# ThreeDigitDisplay.net
KiCad netlist of a schematic drawn in EAGLE
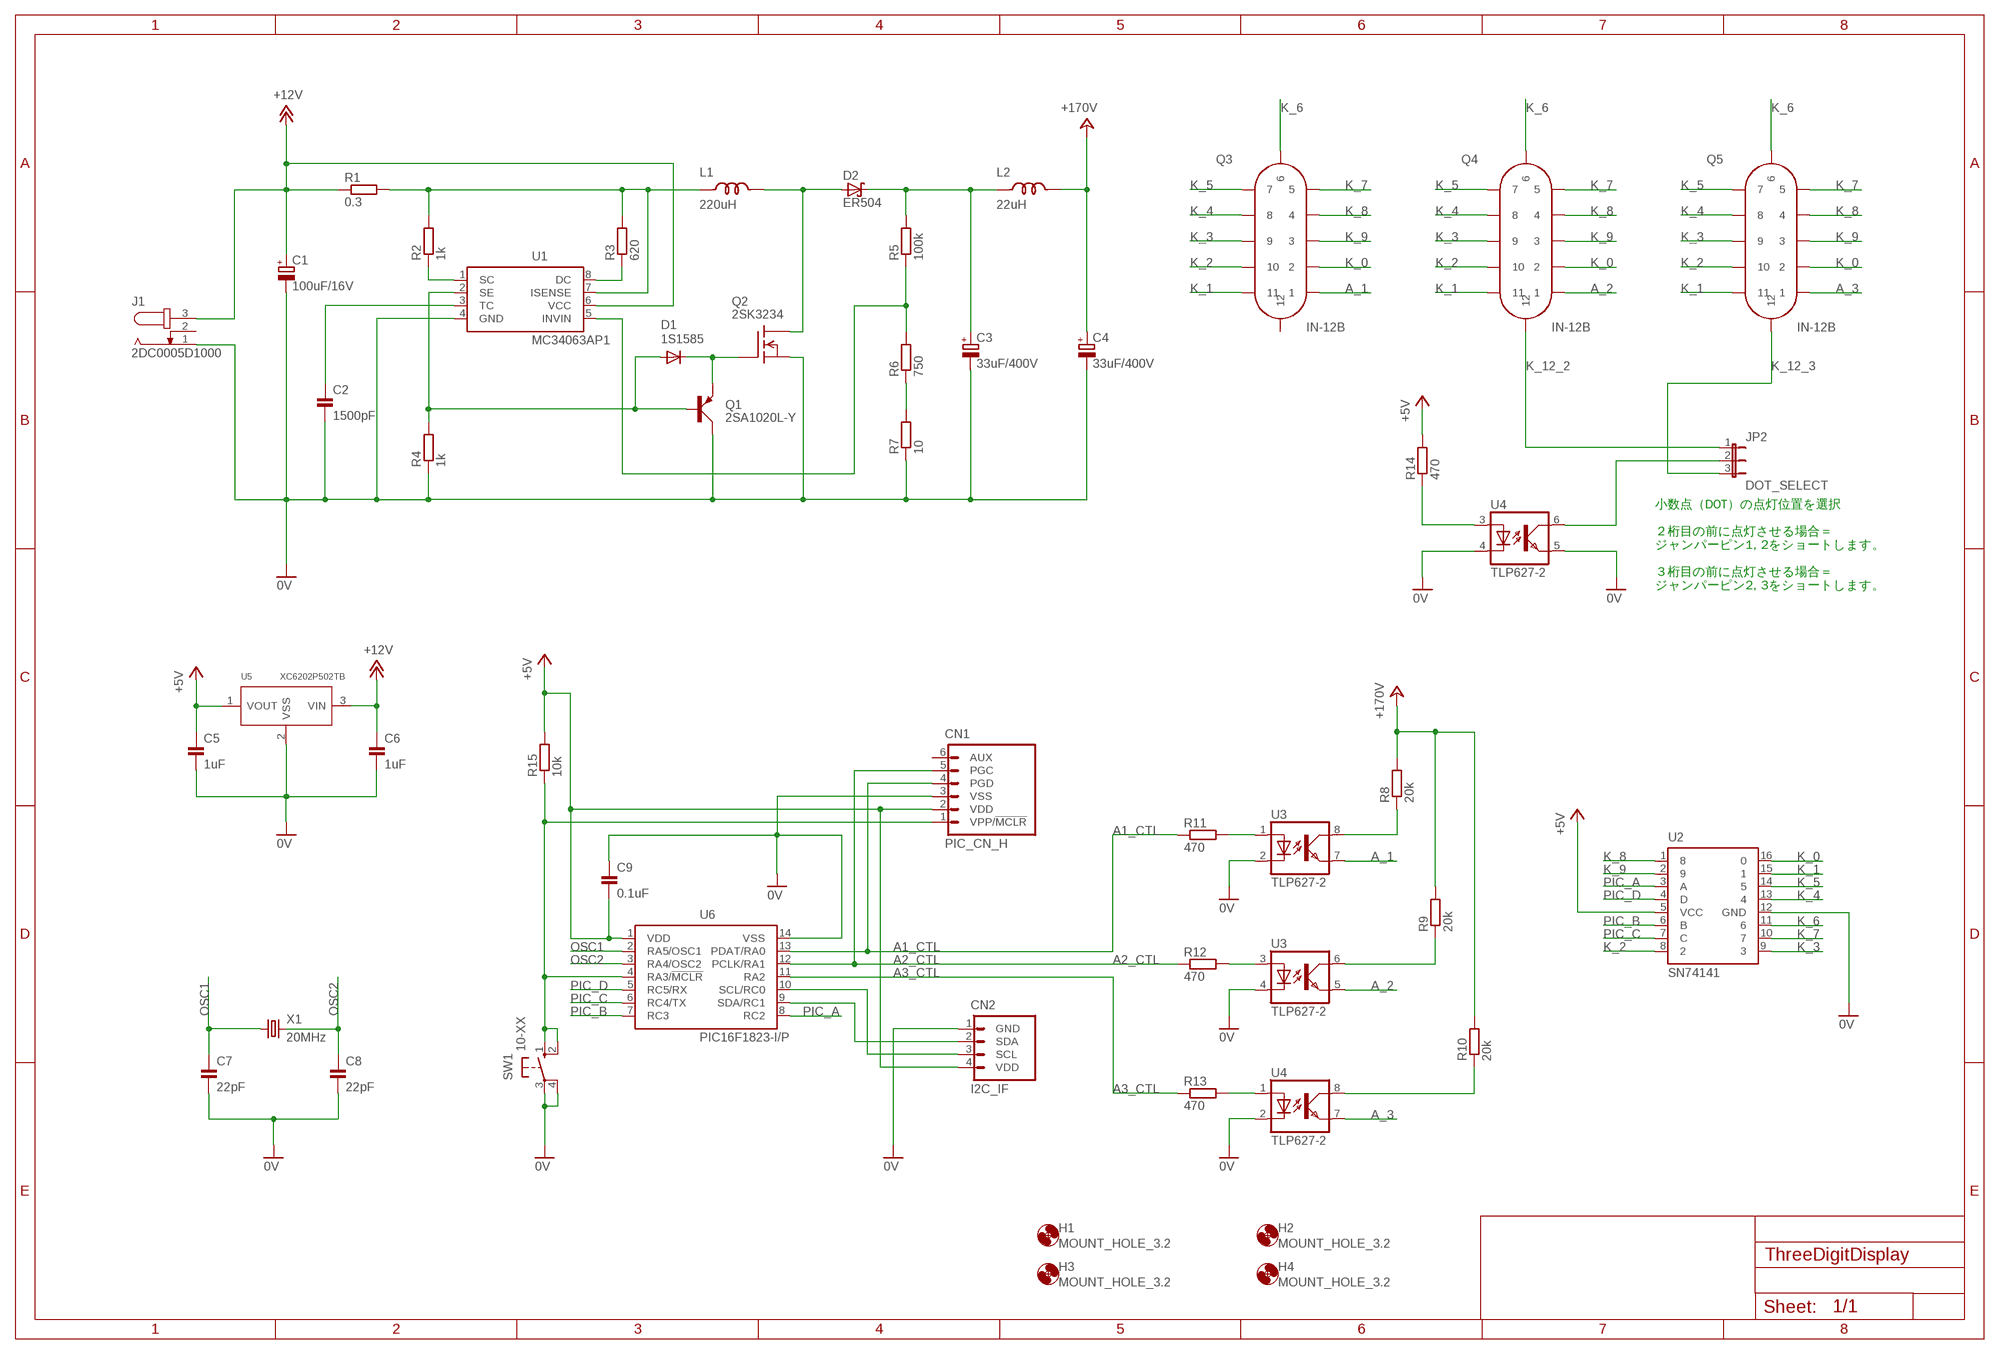
[diagram p0: schematic, sheet 1]

(export (version "E")
  (design (tool "Eeschema 10.0.6"))
  (components
    (comp (ref "C1")
      (value "100uF/16V")
      (footprint "eagle-import:ELECAP_200MIL")
      (libsource (lib "eagle-import") (part "ELECAP_200MIL"))
    )
    (comp (ref "C2")
      (value "1500pF")
      (footprint "eagle-import:CAP_200MIL")
      (libsource (lib "eagle-import") (part "CAP_200MIL"))
    )
    (comp (ref "C3")
      (value "33uF/400V")
      (footprint "eagle-import:ELECAP_300MIL")
      (libsource (lib "eagle-import") (part "ELECAP_300MIL"))
    )
    (comp (ref "C4")
      (value "33uF/400V")
      (footprint "eagle-import:ELECAP_300MIL")
      (libsource (lib "eagle-import") (part "ELECAP_300MIL"))
    )
    (comp (ref "C5")
      (value "1uF")
      (footprint "eagle-import:CAP_200MIL")
      (libsource (lib "eagle-import") (part "CAP_200MIL"))
    )
    (comp (ref "C6")
      (value "1uF")
      (footprint "eagle-import:CAP_200MIL")
      (libsource (lib "eagle-import") (part "CAP_200MIL"))
    )
    (comp (ref "C7")
      (value "22pF")
      (footprint "eagle-import:CAP_200MIL")
      (libsource (lib "eagle-import") (part "CAP_200MIL"))
    )
    (comp (ref "C8")
      (value "22pF")
      (footprint "eagle-import:CAP_200MIL")
      (libsource (lib "eagle-import") (part "CAP_200MIL"))
    )
    (comp (ref "C9")
      (value "0.1uF")
      (footprint "eagle-import:CAP_200MIL")
      (libsource (lib "eagle-import") (part "CAP_200MIL"))
    )
    (comp (ref "CN1")
      (value "PIC_CN_H")
      (footprint "eagle-import:HEADER_6PIN")
      (libsource (lib "eagle-import") (part "PIC_CN_H"))
    )
    (comp (ref "CN2")
      (value "I2C_IF")
      (footprint "eagle-import:I2C_IF")
      (libsource (lib "eagle-import") (part "I2C_IF"))
    )
    (comp (ref "D1")
      (value "1S1585")
      (footprint "eagle-import:DIODE-200MIL")
      (libsource (lib "eagle-import") (part "1S1585"))
    )
    (comp (ref "D2")
      (value "ER504")
      (footprint "eagle-import:DIODE-500MIL")
      (libsource (lib "eagle-import") (part "ER504"))
    )
    (comp (ref "H1")
      (value "MOUNT_HOLE_3.2")
      (footprint "eagle-import:3,2")
      (libsource (lib "eagle-import") (part "MOUNT_HOLE_3.2"))
    )
    (comp (ref "H2")
      (value "MOUNT_HOLE_3.2")
      (footprint "eagle-import:3,2")
      (libsource (lib "eagle-import") (part "MOUNT_HOLE_3.2"))
    )
    (comp (ref "H3")
      (value "MOUNT_HOLE_3.2")
      (footprint "eagle-import:3,2")
      (libsource (lib "eagle-import") (part "MOUNT_HOLE_3.2"))
    )
    (comp (ref "H4")
      (value "MOUNT_HOLE_3.2")
      (footprint "eagle-import:3,2")
      (libsource (lib "eagle-import") (part "MOUNT_HOLE_3.2"))
    )
    (comp (ref "J1")
      (value "2DC0005D1000")
      (footprint "eagle-import:DCJACK_2.1_5.5")
      (libsource (lib "eagle-import") (part "2DC0005D1000"))
    )
    (comp (ref "JP2")
      (value "DOT_SELECT")
      (footprint "eagle-import:JP2")
      (libsource (lib "eagle-import") (part "JP2E"))
    )
    (comp (ref "L1")
      (value "220uH")
      (footprint "eagle-import:TOROID_COIL-300MIL")
      (libsource (lib "eagle-import") (part "TC5026-220UH-050"))
    )
    (comp (ref "L2")
      (value "22uH")
      (footprint "eagle-import:TOROID_COIL-300MIL")
      (libsource (lib "eagle-import") (part "TC5026-22UH-060"))
    )
    (comp (ref "Q1")
      (value "2SA1020L-Y")
      (footprint "eagle-import:TO-92NL")
      (libsource (lib "eagle-import") (part "2SA1020L-Y"))
    )
    (comp (ref "Q2")
      (value "2SK3234")
      (footprint "eagle-import:TO-220")
      (libsource (lib "eagle-import") (part "2SK3234"))
    )
    (comp (ref "Q3")
      (value "IN-12B")
      (footprint "eagle-import:IN-12")
      (libsource (lib "eagle-import") (part "IN-12B"))
    )
    (comp (ref "Q4")
      (value "IN-12B")
      (footprint "eagle-import:IN-12")
      (libsource (lib "eagle-import") (part "IN-12B"))
    )
    (comp (ref "Q5")
      (value "IN-12B")
      (footprint "eagle-import:IN-12")
      (libsource (lib "eagle-import") (part "IN-12B"))
    )
    (comp (ref "R1")
      (value "0.3")
      (footprint "eagle-import:RESISTOR_0411_600MIL")
      (libsource (lib "eagle-import") (part "RESISTOR_600MIL"))
    )
    (comp (ref "R2")
      (value "1k")
      (footprint "eagle-import:RESISTOR_0411_600MIL")
      (libsource (lib "eagle-import") (part "RESISTOR_600MIL"))
    )
    (comp (ref "R3")
      (value "620")
      (footprint "eagle-import:RESISTOR_0411_600MIL")
      (libsource (lib "eagle-import") (part "RESISTOR_600MIL"))
    )
    (comp (ref "R4")
      (value "1k")
      (footprint "eagle-import:RESISTOR_0411_600MIL")
      (libsource (lib "eagle-import") (part "RESISTOR_600MIL"))
    )
    (comp (ref "R5")
      (value "100k")
      (footprint "eagle-import:RESISTOR_0411_600MIL")
      (libsource (lib "eagle-import") (part "RESISTOR_600MIL"))
    )
    (comp (ref "R6")
      (value "750")
      (footprint "eagle-import:RESISTOR_0411_600MIL")
      (libsource (lib "eagle-import") (part "RESISTOR_600MIL"))
    )
    (comp (ref "R7")
      (value "10")
      (footprint "eagle-import:RESISTOR_0411_600MIL")
      (libsource (lib "eagle-import") (part "RESISTOR_600MIL"))
    )
    (comp (ref "R8")
      (value "20k")
      (footprint "eagle-import:RESISTOR_0207_300MIL")
      (libsource (lib "eagle-import") (part "RESISTOR_300MIL"))
    )
    (comp (ref "R9")
      (value "20k")
      (footprint "eagle-import:RESISTOR_0411_600MIL")
      (libsource (lib "eagle-import") (part "RESISTOR_600MIL"))
    )
    (comp (ref "R10")
      (value "20k")
      (footprint "eagle-import:RESISTOR_0207_300MIL")
      (libsource (lib "eagle-import") (part "RESISTOR_300MIL"))
    )
    (comp (ref "R11")
      (value "470")
      (footprint "eagle-import:RESISTOR_0207_300MIL")
      (libsource (lib "eagle-import") (part "RESISTOR_300MIL"))
    )
    (comp (ref "R12")
      (value "470")
      (footprint "eagle-import:RESISTOR_0207_300MIL")
      (libsource (lib "eagle-import") (part "RESISTOR_300MIL"))
    )
    (comp (ref "R13")
      (value "470")
      (footprint "eagle-import:RESISTOR_0207_300MIL")
      (libsource (lib "eagle-import") (part "RESISTOR_300MIL"))
    )
    (comp (ref "R14")
      (value "470")
      (footprint "eagle-import:RESISTOR_0207_300MIL")
      (libsource (lib "eagle-import") (part "RESISTOR_300MIL"))
    )
    (comp (ref "R15")
      (value "10k")
      (footprint "eagle-import:RESISTOR_0207_300MIL")
      (libsource (lib "eagle-import") (part "RESISTOR_300MIL"))
    )
    (comp (ref "SW1")
      (value "10-XX")
      (footprint "eagle-import:B3F-10XX")
      (libsource (lib "eagle-import") (part "10-XX"))
    )
    (comp (ref "U1")
      (value "MC34063AP1")
      (footprint "eagle-import:DIL08")
      (libsource (lib "eagle-import") (part "MC34063AP1"))
    )
    (comp (ref "U2")
      (value "SN74141")
      (footprint "eagle-import:DIL16")
      (libsource (lib "eagle-import") (part "SN74141"))
    )
    (comp (ref "U3")
      (value "TLP627-2")
      (footprint "eagle-import:DIL08")
      (libsource (lib "eagle-import") (part "TLP627-2"))
    )
    (comp (ref "U4")
      (value "TLP627-2")
      (footprint "eagle-import:DIL08")
      (libsource (lib "eagle-import") (part "TLP627-2"))
    )
    (comp (ref "U5")
      (value "XC6202P502TB")
      (footprint "eagle-import:TO92-LINE")
      (libsource (lib "eagle-import") (part "XC6202P502TB"))
    )
    (comp (ref "U6")
      (value "PIC16F1823-I/P")
      (footprint "eagle-import:DIL14")
      (libsource (lib "eagle-import") (part "PIC16F1823-I/P"))
    )
    (comp (ref "X1")
      (value "20MHz")
      (footprint "eagle-import:HC-49_S")
      (libsource (lib "eagle-import") (part "HUSG-20.000-20"))
    )
  )
  (nets
    (net (code "1") (name "+5V") (class "Default")
      (node (ref "C5") (pin "1") (pinfunction "1_1") (pintype "passive"))
      (node (ref "C9") (pin "2") (pinfunction "2_2") (pintype "passive"))
      (node (ref "CN1") (pin "2") (pinfunction "VDD_2") (pintype "passive"))
      (node (ref "CN2") (pin "4") (pinfunction "VDD_4") (pintype "passive"))
      (node (ref "R14") (pin "2") (pinfunction "2_2") (pintype "passive"))
      (node (ref "R15") (pin "2") (pinfunction "2_2") (pintype "passive"))
      (node (ref "U2") (pin "5") (pinfunction "VCC_5") (pintype "passive"))
      (node (ref "U5") (pin "1") (pinfunction "VOUT_1") (pintype "passive"))
      (node (ref "U6") (pin "1") (pinfunction "VDD_1") (pintype "passive"))
    )
    (net (code "2") (name "+12V") (class "Default")
      (node (ref "C1") (pin "+") (pinfunction "+_+") (pintype "passive"))
      (node (ref "C6") (pin "1") (pinfunction "1_1") (pintype "passive"))
      (node (ref "J1") (pin "3") (pinfunction "3_3") (pintype "passive"))
      (node (ref "R1") (pin "1") (pinfunction "1_1") (pintype "passive"))
      (node (ref "U1") (pin "6") (pinfunction "VCC_6") (pintype "passive"))
      (node (ref "U5") (pin "3") (pinfunction "VIN_3") (pintype "passive"))
    )
    (net (code "3") (name "+170V") (class "Default")
      (node (ref "C4") (pin "+") (pinfunction "+_+") (pintype "passive"))
      (node (ref "L2") (pin "2") (pinfunction "2_2") (pintype "passive"))
      (node (ref "R10") (pin "2") (pinfunction "2_2") (pintype "passive"))
      (node (ref "R8") (pin "2") (pinfunction "2_2") (pintype "passive"))
      (node (ref "R9") (pin "2") (pinfunction "2_2") (pintype "passive"))
    )
    (net (code "4") (name "/A1_CTL") (class "Default")
      (node (ref "CN1") (pin "4") (pinfunction "PGD_4") (pintype "bidirectional"))
      (node (ref "R11") (pin "1") (pinfunction "1_1") (pintype "passive"))
      (node (ref "U6") (pin "13") (pinfunction "PDAT/RA0_13") (pintype "bidirectional"))
    )
    (net (code "5") (name "/A2_CTL") (class "Default")
      (node (ref "CN1") (pin "5") (pinfunction "PGC_5") (pintype "input"))
      (node (ref "R12") (pin "1") (pinfunction "1_1") (pintype "passive"))
      (node (ref "U6") (pin "12") (pinfunction "PCLK/RA1_12") (pintype "bidirectional"))
    )
    (net (code "6") (name "/A3_CTL") (class "Default")
      (node (ref "R13") (pin "1") (pinfunction "1_1") (pintype "passive"))
      (node (ref "U6") (pin "11") (pinfunction "RA2_11") (pintype "bidirectional"))
    )
    (net (code "7") (name "/A_1") (class "Default")
      (node (ref "Q3") (pin "1") (pinfunction "1_1") (pintype "passive"))
      (node (ref "U3") (pin "7") (pinfunction "EMIT_7") (pintype "passive"))
    )
    (net (code "8") (name "/A_2") (class "Default")
      (node (ref "Q4") (pin "1") (pinfunction "1_1") (pintype "passive"))
      (node (ref "U3") (pin "5") (pinfunction "EMIT_5") (pintype "passive"))
    )
    (net (code "9") (name "/A_3") (class "Default")
      (node (ref "Q5") (pin "1") (pinfunction "1_1") (pintype "passive"))
      (node (ref "U4") (pin "7") (pinfunction "EMIT_7") (pintype "passive"))
    )
    (net (code "10") (name "/K_0") (class "Default")
      (node (ref "Q3") (pin "2") (pinfunction "2_2") (pintype "passive"))
      (node (ref "Q4") (pin "2") (pinfunction "2_2") (pintype "passive"))
      (node (ref "Q5") (pin "2") (pinfunction "2_2") (pintype "passive"))
      (node (ref "U2") (pin "16") (pinfunction "0_16") (pintype "passive"))
    )
    (net (code "11") (name "/K_1") (class "Default")
      (node (ref "Q3") (pin "11") (pinfunction "11_11") (pintype "passive"))
      (node (ref "Q4") (pin "11") (pinfunction "11_11") (pintype "passive"))
      (node (ref "Q5") (pin "11") (pinfunction "11_11") (pintype "passive"))
      (node (ref "U2") (pin "15") (pinfunction "1_15") (pintype "passive"))
    )
    (net (code "12") (name "/K_2") (class "Default")
      (node (ref "Q3") (pin "10") (pinfunction "10_10") (pintype "passive"))
      (node (ref "Q4") (pin "10") (pinfunction "10_10") (pintype "passive"))
      (node (ref "Q5") (pin "10") (pinfunction "10_10") (pintype "passive"))
      (node (ref "U2") (pin "8") (pinfunction "2_8") (pintype "passive"))
    )
    (net (code "13") (name "/K_3") (class "Default")
      (node (ref "Q3") (pin "9") (pinfunction "9_9") (pintype "passive"))
      (node (ref "Q4") (pin "9") (pinfunction "9_9") (pintype "passive"))
      (node (ref "Q5") (pin "9") (pinfunction "9_9") (pintype "passive"))
      (node (ref "U2") (pin "9") (pinfunction "3_9") (pintype "passive"))
    )
    (net (code "14") (name "/K_4") (class "Default")
      (node (ref "Q3") (pin "8") (pinfunction "8_8") (pintype "passive"))
      (node (ref "Q4") (pin "8") (pinfunction "8_8") (pintype "passive"))
      (node (ref "Q5") (pin "8") (pinfunction "8_8") (pintype "passive"))
      (node (ref "U2") (pin "13") (pinfunction "4_13") (pintype "passive"))
    )
    (net (code "15") (name "/K_5") (class "Default")
      (node (ref "Q3") (pin "7") (pinfunction "7_7") (pintype "passive"))
      (node (ref "Q4") (pin "7") (pinfunction "7_7") (pintype "passive"))
      (node (ref "Q5") (pin "7") (pinfunction "7_7") (pintype "passive"))
      (node (ref "U2") (pin "14") (pinfunction "5_14") (pintype "passive"))
    )
    (net (code "16") (name "/K_6") (class "Default")
      (node (ref "Q3") (pin "6") (pinfunction "6_6") (pintype "passive"))
      (node (ref "Q4") (pin "6") (pinfunction "6_6") (pintype "passive"))
      (node (ref "Q5") (pin "6") (pinfunction "6_6") (pintype "passive"))
      (node (ref "U2") (pin "11") (pinfunction "6_11") (pintype "passive"))
    )
    (net (code "17") (name "/K_7") (class "Default")
      (node (ref "Q3") (pin "5") (pinfunction "5_5") (pintype "passive"))
      (node (ref "Q4") (pin "5") (pinfunction "5_5") (pintype "passive"))
      (node (ref "Q5") (pin "5") (pinfunction "5_5") (pintype "passive"))
      (node (ref "U2") (pin "10") (pinfunction "7_10") (pintype "passive"))
    )
    (net (code "18") (name "/K_8") (class "Default")
      (node (ref "Q3") (pin "4") (pinfunction "4_4") (pintype "passive"))
      (node (ref "Q4") (pin "4") (pinfunction "4_4") (pintype "passive"))
      (node (ref "Q5") (pin "4") (pinfunction "4_4") (pintype "passive"))
      (node (ref "U2") (pin "1") (pinfunction "8_1") (pintype "passive"))
    )
    (net (code "19") (name "/K_9") (class "Default")
      (node (ref "Q3") (pin "3") (pinfunction "3_3") (pintype "passive"))
      (node (ref "Q4") (pin "3") (pinfunction "3_3") (pintype "passive"))
      (node (ref "Q5") (pin "3") (pinfunction "3_3") (pintype "passive"))
      (node (ref "U2") (pin "2") (pinfunction "9_2") (pintype "passive"))
    )
    (net (code "20") (name "/K_12_2") (class "Default")
      (node (ref "JP2") (pin "1") (pinfunction "1_1") (pintype "passive"))
      (node (ref "Q4") (pin "12") (pinfunction "12_12") (pintype "passive"))
    )
    (net (code "21") (name "/K_12_3") (class "Default")
      (node (ref "JP2") (pin "3") (pinfunction "3_3") (pintype "passive"))
      (node (ref "Q5") (pin "12") (pinfunction "12_12") (pintype "passive"))
    )
    (net (code "22") (name "/OSC1") (class "Default")
      (node (ref "C7") (pin "1") (pinfunction "1_1") (pintype "passive"))
      (node (ref "U6") (pin "2") (pinfunction "RA5/OSC1_2") (pintype "bidirectional"))
      (node (ref "X1") (pin "1") (pinfunction "1_1") (pintype "passive"))
    )
    (net (code "23") (name "/OSC2") (class "Default")
      (node (ref "C8") (pin "1") (pinfunction "1_1") (pintype "passive"))
      (node (ref "U6") (pin "3") (pinfunction "RA4/OSC2_3") (pintype "bidirectional"))
      (node (ref "X1") (pin "2") (pinfunction "2_2") (pintype "passive"))
    )
    (net (code "24") (name "/PIC_A") (class "Default")
      (node (ref "U2") (pin "3") (pinfunction "A_3") (pintype "input"))
      (node (ref "U6") (pin "8") (pinfunction "RC2_8") (pintype "bidirectional"))
    )
    (net (code "25") (name "/PIC_B") (class "Default")
      (node (ref "U2") (pin "6") (pinfunction "B_6") (pintype "input"))
      (node (ref "U6") (pin "7") (pinfunction "RC3_7") (pintype "bidirectional"))
    )
    (net (code "26") (name "/PIC_C") (class "Default")
      (node (ref "U2") (pin "7") (pinfunction "C_7") (pintype "input"))
      (node (ref "U6") (pin "6") (pinfunction "RC4/TX_6") (pintype "bidirectional"))
    )
    (net (code "27") (name "/PIC_D") (class "Default")
      (node (ref "U2") (pin "4") (pinfunction "D_4") (pintype "input"))
      (node (ref "U6") (pin "5") (pinfunction "RC5/RX_5") (pintype "bidirectional"))
    )
    (net (code "28") (name "0V") (class "Default")
      (node (ref "C1") (pin "-") (pinfunction "-_-") (pintype "passive"))
      (node (ref "C2") (pin "2") (pinfunction "2_2") (pintype "passive"))
      (node (ref "C3") (pin "-") (pinfunction "-_-") (pintype "passive"))
      (node (ref "C4") (pin "-") (pinfunction "-_-") (pintype "passive"))
      (node (ref "C5") (pin "2") (pinfunction "2_2") (pintype "passive"))
      (node (ref "C6") (pin "2") (pinfunction "2_2") (pintype "passive"))
      (node (ref "C7") (pin "2") (pinfunction "2_2") (pintype "passive"))
      (node (ref "C8") (pin "2") (pinfunction "2_2") (pintype "passive"))
      (node (ref "C9") (pin "1") (pinfunction "1_1") (pintype "passive"))
      (node (ref "CN1") (pin "3") (pinfunction "VSS_3") (pintype "passive"))
      (node (ref "CN2") (pin "1") (pinfunction "GND_1") (pintype "passive"))
      (node (ref "J1") (pin "1") (pinfunction "1_1") (pintype "passive"))
      (node (ref "Q1") (pin "2") (pinfunction "C_2") (pintype "passive"))
      (node (ref "Q2") (pin "3") (pinfunction "S_3") (pintype "passive"))
      (node (ref "R4") (pin "1") (pinfunction "1_1") (pintype "passive"))
      (node (ref "R7") (pin "1") (pinfunction "1_1") (pintype "passive"))
      (node (ref "SW1") (pin "3") (pinfunction "P_3") (pintype "passive"))
      (node (ref "SW1") (pin "4") (pinfunction "P1_4") (pintype "passive"))
      (node (ref "U1") (pin "4") (pinfunction "GND_4") (pintype "passive"))
      (node (ref "U2") (pin "12") (pinfunction "GND_12") (pintype "passive"))
      (node (ref "U3") (pin "2") (pinfunction "C_2") (pintype "passive"))
      (node (ref "U3") (pin "4") (pinfunction "C_4") (pintype "passive"))
      (node (ref "U4") (pin "2") (pinfunction "C_2") (pintype "passive"))
      (node (ref "U4") (pin "4") (pinfunction "C_4") (pintype "passive"))
      (node (ref "U4") (pin "5") (pinfunction "EMIT_5") (pintype "passive"))
      (node (ref "U5") (pin "2") (pinfunction "VSS_2") (pintype "passive"))
      (node (ref "U6") (pin "14") (pinfunction "VSS_14") (pintype "passive"))
    )
    (net (code "29") (name "Net-(C3-Pad+)") (class "Default")
      (node (ref "C3") (pin "+") (pinfunction "+_+") (pintype "passive"))
      (node (ref "D2") (pin "C") (pinfunction "C_C") (pintype "passive"))
      (node (ref "L2") (pin "1") (pinfunction "1_1") (pintype "passive"))
      (node (ref "R5") (pin "2") (pinfunction "2_2") (pintype "passive"))
    )
    (net (code "30") (name "Net-(CN1-VPP{slash}~{MCLR})") (class "Default")
      (node (ref "CN1") (pin "1") (pinfunction "VPP/~{MCLR}_1") (pintype "input"))
      (node (ref "R15") (pin "1") (pinfunction "1_1") (pintype "passive"))
      (node (ref "SW1") (pin "1") (pinfunction "S_1") (pintype "passive"))
      (node (ref "SW1") (pin "2") (pinfunction "S1_2") (pintype "passive"))
      (node (ref "U6") (pin "4") (pinfunction "RA3/~{MCLR}_4") (pintype "bidirectional"))
    )
    (net (code "31") (name "Net-(CN2-SCL)") (class "Default")
      (node (ref "CN2") (pin "3") (pinfunction "SCL_3") (pintype "bidirectional"))
      (node (ref "U6") (pin "10") (pinfunction "SCL/RC0_10") (pintype "bidirectional"))
    )
    (net (code "32") (name "Net-(CN2-SDA)") (class "Default")
      (node (ref "CN2") (pin "2") (pinfunction "SDA_2") (pintype "bidirectional"))
      (node (ref "U6") (pin "9") (pinfunction "SDA/RC1_9") (pintype "bidirectional"))
    )
    (net (code "33") (name "Net-(Q1-B)") (class "Default")
      (node (ref "D1") (pin "A") (pinfunction "A_A") (pintype "passive"))
      (node (ref "Q1") (pin "3") (pinfunction "B_3") (pintype "passive"))
      (node (ref "R4") (pin "2") (pinfunction "2_2") (pintype "passive"))
      (node (ref "U1") (pin "2") (pinfunction "SE_2") (pintype "passive"))
    )
    (net (code "34") (name "Net-(Q1-E)") (class "Default")
      (node (ref "D1") (pin "C") (pinfunction "C_C") (pintype "passive"))
      (node (ref "Q1") (pin "1") (pinfunction "E_1") (pintype "passive"))
      (node (ref "Q2") (pin "1") (pinfunction "G_1") (pintype "passive"))
    )
    (net (code "35") (name "Net-(Q2-D)") (class "Default")
      (node (ref "D2") (pin "A") (pinfunction "A_A") (pintype "passive"))
      (node (ref "L1") (pin "2") (pinfunction "2_2") (pintype "passive"))
      (node (ref "Q2") (pin "2") (pinfunction "D_2") (pintype "passive"))
    )
    (net (code "36") (name "Net-(R6-Pad1)") (class "Default")
      (node (ref "R6") (pin "1") (pinfunction "1_1") (pintype "passive"))
      (node (ref "R7") (pin "2") (pinfunction "2_2") (pintype "passive"))
    )
    (net (code "37") (name "Net-(U1-DC)") (class "Default")
      (node (ref "R3") (pin "1") (pinfunction "1_1") (pintype "passive"))
      (node (ref "U1") (pin "8") (pinfunction "DC_8") (pintype "passive"))
    )
    (net (code "38") (name "Net-(U1-INVIN)") (class "Default")
      (node (ref "R5") (pin "1") (pinfunction "1_1") (pintype "passive"))
      (node (ref "R6") (pin "2") (pinfunction "2_2") (pintype "passive"))
      (node (ref "U1") (pin "5") (pinfunction "INVIN_5") (pintype "passive"))
    )
    (net (code "39") (name "Net-(U1-ISENSE)") (class "Default")
      (node (ref "L1") (pin "1") (pinfunction "1_1") (pintype "passive"))
      (node (ref "R1") (pin "2") (pinfunction "2_2") (pintype "passive"))
      (node (ref "R2") (pin "2") (pinfunction "2_2") (pintype "passive"))
      (node (ref "R3") (pin "2") (pinfunction "2_2") (pintype "passive"))
      (node (ref "U1") (pin "7") (pinfunction "ISENSE_7") (pintype "passive"))
    )
    (net (code "40") (name "Net-(U1-SC)") (class "Default")
      (node (ref "R2") (pin "1") (pinfunction "1_1") (pintype "passive"))
      (node (ref "U1") (pin "1") (pinfunction "SC_1") (pintype "passive"))
    )
    (net (code "41") (name "Net-(U1-TC)") (class "Default")
      (node (ref "C2") (pin "1") (pinfunction "1_1") (pintype "passive"))
      (node (ref "U1") (pin "3") (pinfunction "TC_3") (pintype "passive"))
    )
    (net (code "42") (name "Net-(U3A-A)") (class "Default")
      (node (ref "R11") (pin "2") (pinfunction "2_2") (pintype "passive"))
      (node (ref "U3") (pin "1") (pinfunction "A_1") (pintype "passive"))
    )
    (net (code "43") (name "Net-(U3A-COL)") (class "Default")
      (node (ref "R8") (pin "1") (pinfunction "1_1") (pintype "passive"))
      (node (ref "U3") (pin "8") (pinfunction "COL_8") (pintype "passive"))
    )
    (net (code "44") (name "Net-(U3B-A)") (class "Default")
      (node (ref "R12") (pin "2") (pinfunction "2_2") (pintype "passive"))
      (node (ref "U3") (pin "3") (pinfunction "A_3") (pintype "passive"))
    )
    (net (code "45") (name "Net-(U3B-COL)") (class "Default")
      (node (ref "R9") (pin "1") (pinfunction "1_1") (pintype "passive"))
      (node (ref "U3") (pin "6") (pinfunction "COL_6") (pintype "passive"))
    )
    (net (code "46") (name "Net-(U4A-A)") (class "Default")
      (node (ref "R13") (pin "2") (pinfunction "2_2") (pintype "passive"))
      (node (ref "U4") (pin "1") (pinfunction "A_1") (pintype "passive"))
    )
    (net (code "47") (name "Net-(U4A-COL)") (class "Default")
      (node (ref "R10") (pin "1") (pinfunction "1_1") (pintype "passive"))
      (node (ref "U4") (pin "8") (pinfunction "COL_8") (pintype "passive"))
    )
    (net (code "48") (name "Net-(U4B-A)") (class "Default")
      (node (ref "R14") (pin "1") (pinfunction "1_1") (pintype "passive"))
      (node (ref "U4") (pin "3") (pinfunction "A_3") (pintype "passive"))
    )
    (net (code "49") (name "Net-(U4B-COL)") (class "Default")
      (node (ref "JP2") (pin "2") (pinfunction "2_2") (pintype "passive"))
      (node (ref "U4") (pin "6") (pinfunction "COL_6") (pintype "passive"))
    )
    (net (code "50") (name "unconnected-(CN1-AUX-Pad6)") (class "Default")
      (node (ref "CN1") (pin "6") (pinfunction "AUX_6") (pintype "bidirectional"))
    )
    (net (code "51") (name "unconnected-(J1-Pad2)") (class "Default")
      (node (ref "J1") (pin "2") (pinfunction "2_2") (pintype "passive"))
    )
    (net (code "52") (name "unconnected-(Q3-Pad12)") (class "Default")
      (node (ref "Q3") (pin "12") (pinfunction "12_12") (pintype "passive"))
    )
  )
)
